# 28-RS485.net
KiCad netlist of a schematic drawn in Altium Designer
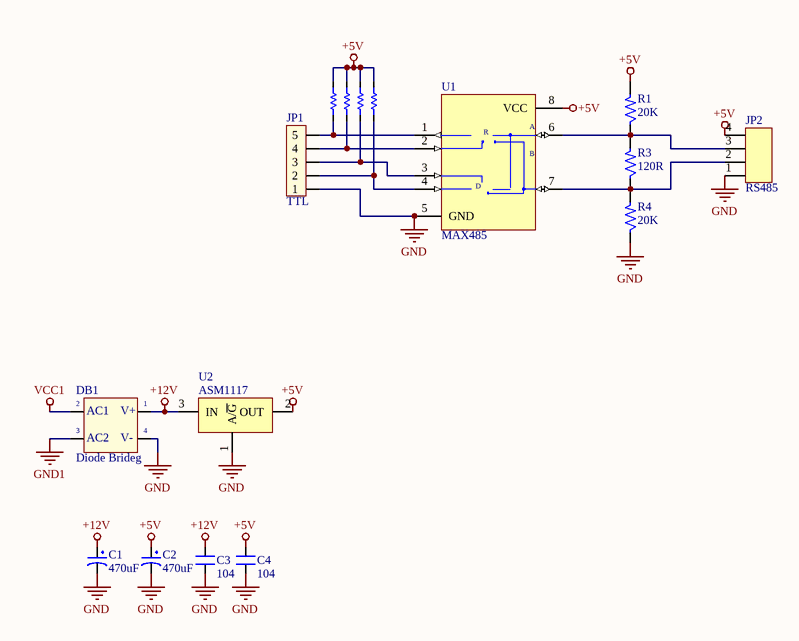
[diagram p0: 28-RS485.SchDoc]

(export (version "E")
  (design (tool "Eeschema 10.0.6"))
  (components
    (comp (ref "C1")
      (value "470uF")
      (footprint "C-ALU-D6.5")
      (description "Cap P  0,1uF < 22uF , 16 - 50V")
      (libsource (lib "PART") (part "CP1"))
    )
    (comp (ref "C2")
      (value "470uF")
      (footprint "C-ALU-D6.5")
      (description "Cap P  0,1uF < 22uF , 16 - 50V")
      (libsource (lib "PART") (part "CP1"))
    )
    (comp (ref "C3")
      (value "104")
      (footprint "C-0805")
      (fields (field (name "DESIGNED BY") "VanDungEvn"))
      (libsource (lib "syhaunguyen") (part "CN"))
    )
    (comp (ref "C4")
      (value "104")
      (footprint "C-0805")
      (fields (field (name "DESIGNED BY") "VanDungEvn"))
      (libsource (lib "syhaunguyen") (part "CN"))
    )
    (comp (ref "DB1")
      (value "Diode Brideg")
      (footprint "D-DB-1A-SMD")
      (description "Convert AC to DC voltage, 4 pin")
      (libsource (lib "PART") (part "DB"))
    )
    (comp (ref "JP1") (value "TTL") (footprint "JP5") (libsource (lib "syhaunguyen") (part "JP5")))
    (comp (ref "JP2") (value "RS485") (footprint "JP4") (libsource (lib "doAnTotNghiep2017Lib") (part "JP4")))
    (comp (ref "R1")
      (value "20K")
      (footprint "R-0805")
      (description "Resistor 1/4W")
      (libsource (lib "PART") (part "R"))
    )
    (comp (ref "R2")
      (value "10K")
      (footprint "R-Array-0603-4")
      (description "RES ARRAY 4 RES 330 OHM 1206")
      (fields
        (field (name "DIGI-KEY PART NUMBER") "Y9331TR-ND")
        (field (name "MANUFACTURER") "Panasonic Electronic Components")
      )
      (libsource (lib "Dlib") (part "Res Array 4"))
    )
    (comp (ref "R3")
      (value "120R")
      (footprint "R-0805")
      (description "Resistor 1/4W")
      (libsource (lib "PART") (part "R"))
    )
    (comp (ref "R4")
      (value "20K")
      (footprint "R-0805")
      (description "Resistor 1/4W")
      (libsource (lib "PART") (part "R"))
    )
    (comp (ref "U1") (value "MAX485") (footprint "SOP-8") (libsource (lib "Dlib") (part "MAX485")))
    (comp (ref "U2")
      (value "ASM1117")
      (footprint "TO-252")
      (libsource (lib "doAnTotNghiep2017Lib") (part "ASM1117"))
    )
  )
  (nets
    (net (code "1") (name "+5V") (class "Default")
      (node (ref "C2") (pin "1") (pinfunction "1_1") (pintype "passive"))
      (node (ref "C4") (pin "2") (pinfunction "2_2") (pintype "passive"))
      (node (ref "JP2") (pin "4") (pintype "passive"))
      (node (ref "R1") (pin "2") (pinfunction "2_2") (pintype "passive"))
      (node (ref "R2") (pin "2") (pinfunction "2_2") (pintype "passive"))
      (node (ref "R2") (pin "4") (pinfunction "2_4") (pintype "passive"))
      (node (ref "R2") (pin "6") (pinfunction "2_6") (pintype "passive"))
      (node (ref "R2") (pin "8") (pinfunction "2_8") (pintype "passive"))
      (node (ref "U1") (pin "8") (pinfunction "VCC_8") (pintype "power_in"))
      (node (ref "U2") (pin "2") (pinfunction "OUT_2") (pintype "passive"))
    )
    (net (code "2") (name "+12V") (class "Default")
      (node (ref "C1") (pin "1") (pinfunction "1_1") (pintype "passive"))
      (node (ref "C3") (pin "2") (pinfunction "2_2") (pintype "passive"))
      (node (ref "DB1") (pin "3") (pinfunction "AC2_3") (pintype "passive"))
      (node (ref "U2") (pin "3") (pinfunction "IN_3") (pintype "passive"))
    )
    (net (code "3") (name "GND") (class "Default")
      (node (ref "C1") (pin "2") (pinfunction "2_2") (pintype "passive"))
      (node (ref "C2") (pin "2") (pinfunction "2_2") (pintype "passive"))
      (node (ref "C3") (pin "1") (pinfunction "1_1") (pintype "passive"))
      (node (ref "C4") (pin "1") (pinfunction "1_1") (pintype "passive"))
      (node (ref "DB1") (pin "4") (pinfunction "-V_OUT_4") (pintype "passive"))
      (node (ref "JP1") (pin "1") (pinfunction "1_1") (pintype "passive"))
      (node (ref "JP2") (pin "1") (pintype "passive"))
      (node (ref "R4") (pin "1") (pinfunction "1_1") (pintype "passive"))
      (node (ref "U1") (pin "5") (pinfunction "GND_5") (pintype "power_in"))
      (node (ref "U2") (pin "1") (pinfunction "A/~{G}_1") (pintype "passive"))
    )
    (net (code "4") (name "GND1") (class "Default")
      (node (ref "DB1") (pin "1") (pinfunction "+V_OUT_1") (pintype "passive"))
    )
    (net (code "5") (name "Net-(R2B-1)") (class "Default")
      (node (ref "JP1") (pin "5") (pinfunction "5_5") (pintype "passive"))
      (node (ref "R2") (pin "3") (pinfunction "1_3") (pintype "passive"))
      (node (ref "U1") (pin "1") (pinfunction "RO_1") (pintype "output"))
    )
    (net (code "6") (name "Net-(R2C-1)") (class "Default")
      (node (ref "JP1") (pin "4") (pinfunction "4_4") (pintype "passive"))
      (node (ref "R2") (pin "5") (pinfunction "1_5") (pintype "passive"))
      (node (ref "U1") (pin "2") (pinfunction "~{RE}_2") (pintype "input"))
    )
    (net (code "7") (name "Net-(R2D-1)") (class "Default")
      (node (ref "JP1") (pin "3") (pinfunction "3_3") (pintype "passive"))
      (node (ref "R2") (pin "7") (pinfunction "1_7") (pintype "passive"))
      (node (ref "U1") (pin "3") (pinfunction "DE_3") (pintype "input"))
    )
    (net (code "8") (name "Net-(U1-A)") (class "Default")
      (node (ref "JP2") (pin "3") (pintype "passive"))
      (node (ref "R1") (pin "1") (pinfunction "1_1") (pintype "passive"))
      (node (ref "R3") (pin "2") (pinfunction "2_2") (pintype "passive"))
      (node (ref "U1") (pin "6") (pinfunction "A_6") (pintype "bidirectional"))
    )
    (net (code "9") (name "Net-(U1-B)") (class "Default")
      (node (ref "JP2") (pin "2") (pintype "passive"))
      (node (ref "R3") (pin "1") (pinfunction "1_1") (pintype "passive"))
      (node (ref "R4") (pin "2") (pinfunction "2_2") (pintype "passive"))
      (node (ref "U1") (pin "7") (pinfunction "B_7") (pintype "bidirectional"))
    )
    (net (code "10") (name "Net-(U1-DI)") (class "Default")
      (node (ref "JP1") (pin "2") (pinfunction "2_2") (pintype "passive"))
      (node (ref "R2") (pin "1") (pinfunction "1_1") (pintype "passive"))
      (node (ref "U1") (pin "4") (pinfunction "DI_4") (pintype "input"))
    )
    (net (code "11") (name "VCC1") (class "Default")
      (node (ref "DB1") (pin "2") (pinfunction "AC1_2") (pintype "passive"))
    )
  )
)
